# brainwave_daughter_for_kossel_mini.net
KiCad netlist of a schematic drawn in EAGLE
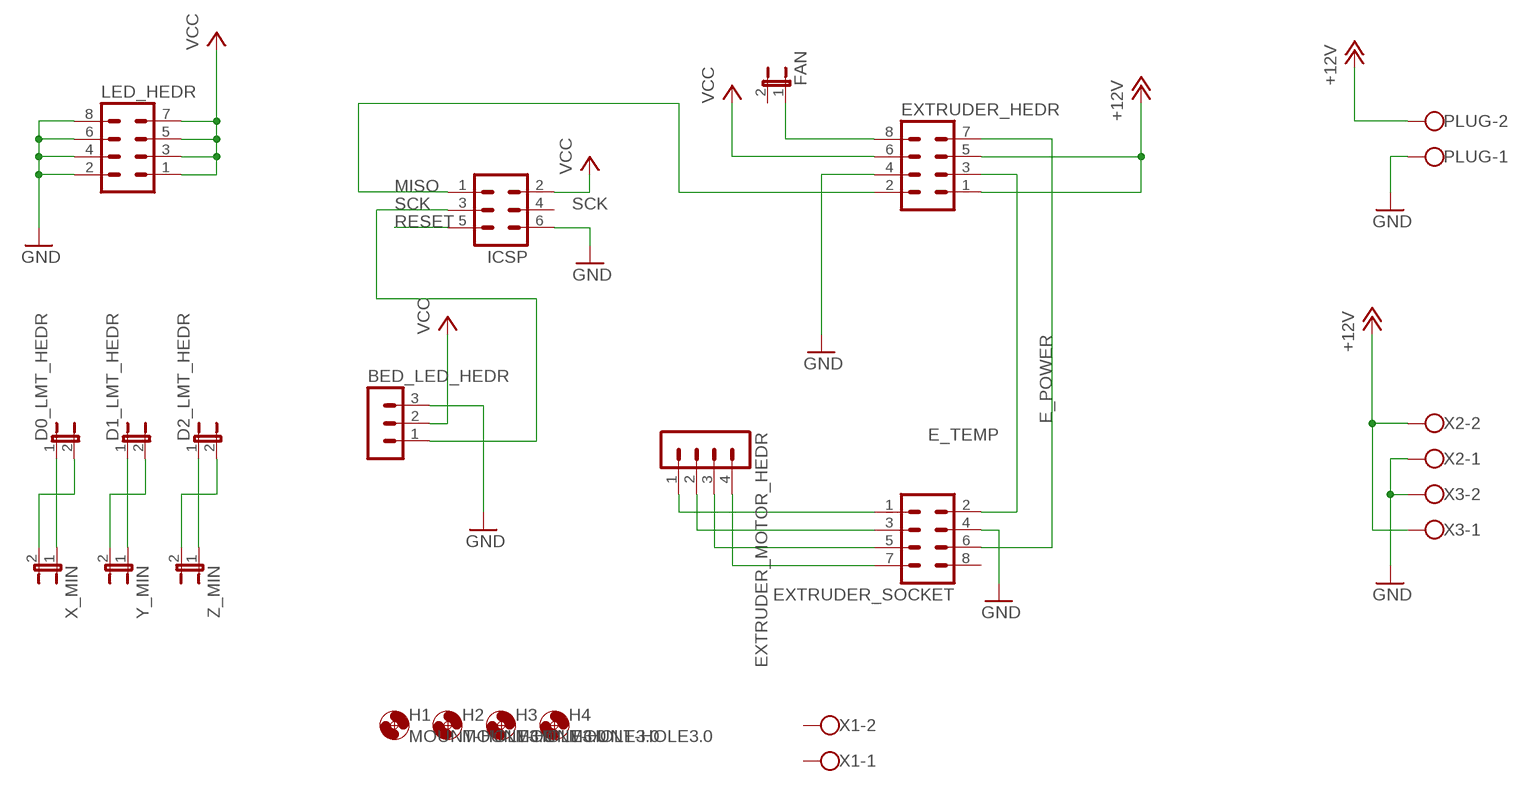
[diagram p0: schematic, sheet 1]

(export (version "E")
  (design (tool "Eeschema 10.0.6"))
  (components
    (comp (ref "BED_LED_HEDR")
      (value "MA03-1")
      (footprint "eagle-import:MA03-1")
      (libsource (lib "eagle-import") (part "MA03-1"))
    )
    (comp (ref "D0_LMT_HEDR")
      (value "JP1E")
      (footprint "eagle-import:JP1")
      (libsource (lib "eagle-import") (part "JP1E"))
    )
    (comp (ref "D1_LMT_HEDR")
      (value "JP1E")
      (footprint "eagle-import:JP1")
      (libsource (lib "eagle-import") (part "JP1E"))
    )
    (comp (ref "D2_LMT_HEDR")
      (value "JP1E")
      (footprint "eagle-import:JP1")
      (libsource (lib "eagle-import") (part "JP1E"))
    )
    (comp (ref "EXTRUDER_HEDR")
      (value "MA04-2")
      (footprint "eagle-import:MA04-2")
      (libsource (lib "eagle-import") (part "MA04-2"))
    )
    (comp (ref "EXTRUDER_MOTOR_HEDR")
      (value "MA04-1")
      (footprint "eagle-import:MA04-1")
      (libsource (lib "eagle-import") (part "MA04-1"))
    )
    (comp (ref "EXTRUDER_SOCKET")
      (value "MA04-2")
      (footprint "eagle-import:MA04-2")
      (libsource (lib "eagle-import") (part "MA04-2"))
    )
    (comp (ref "FAN")
      (value "JP1E")
      (footprint "eagle-import:JP1")
      (libsource (lib "eagle-import") (part "JP1E"))
    )
    (comp (ref "H1")
      (value "MOUNT-HOLE3.0")
      (footprint "eagle-import:3,0")
      (libsource (lib "eagle-import") (part "MOUNT-HOLE3.0"))
    )
    (comp (ref "H2")
      (value "MOUNT-HOLE3.0")
      (footprint "eagle-import:3,0")
      (libsource (lib "eagle-import") (part "MOUNT-HOLE3.0"))
    )
    (comp (ref "H3")
      (value "MOUNT-HOLE3.0")
      (footprint "eagle-import:3,0")
      (libsource (lib "eagle-import") (part "MOUNT-HOLE3.0"))
    )
    (comp (ref "H4")
      (value "MOUNT-HOLE3.0")
      (footprint "eagle-import:3,0")
      (libsource (lib "eagle-import") (part "MOUNT-HOLE3.0"))
    )
    (comp (ref "ICSP")
      (value "MA03-2")
      (footprint "eagle-import:MA03-2")
      (libsource (lib "eagle-import") (part "MA03-2"))
    )
    (comp (ref "LED_HEDR")
      (value "MA04-2")
      (footprint "eagle-import:MA04-2")
      (libsource (lib "eagle-import") (part "MA04-2"))
    )
    (comp (ref "PLUG")
      (value "W237-102")
      (footprint "eagle-import:W237-102")
      (fields (field (name "MPN") "237-102"))
      (libsource (lib "eagle-import") (part "W237-102"))
    )
    (comp (ref "X1")
      (value "W237-102")
      (footprint "eagle-import:W237-102")
      (fields
        (field (name "MPN") "237-102")
        (field (name "MPN_1") "237-102")
        (field (name "OC_FARNELL") "unknown")
        (field (name "OC_NEWARK") "70K9898")
      )
      (libsource (lib "eagle-import") (part "W237-102"))
    )
    (comp (ref "X2")
      (value "W237-102")
      (footprint "eagle-import:W237-102")
      (fields (field (name "MPN") "237-102"))
      (libsource (lib "eagle-import") (part "W237-102"))
    )
    (comp (ref "X3")
      (value "W237-102")
      (footprint "eagle-import:W237-102")
      (fields
        (field (name "MPN") "237-102")
        (field (name "MPN_1") "237-102")
        (field (name "OC_FARNELL") "unknown")
        (field (name "OC_NEWARK") "70K9898")
      )
      (libsource (lib "eagle-import") (part "W237-102"))
    )
    (comp (ref "X_MIN")
      (value "JP1E")
      (footprint "eagle-import:JP1")
      (libsource (lib "eagle-import") (part "JP1E"))
    )
    (comp (ref "Y_MIN")
      (value "JP1E")
      (footprint "eagle-import:JP1")
      (libsource (lib "eagle-import") (part "JP1E"))
    )
    (comp (ref "Z_MIN")
      (value "JP1E")
      (footprint "eagle-import:JP1")
      (libsource (lib "eagle-import") (part "JP1E"))
    )
  )
  (nets
    (net (code "1") (name "+12V") (class "Default")
      (node (ref "EXTRUDER_HEDR") (pin "1") (pinfunction "1_1") (pintype "passive"))
      (node (ref "EXTRUDER_HEDR") (pin "5") (pinfunction "5_5") (pintype "passive"))
      (node (ref "PLUG") (pin "2") (pinfunction "KL_2") (pintype "passive"))
      (node (ref "X2") (pin "2") (pinfunction "KL_2") (pintype "passive"))
      (node (ref "X3") (pin "1") (pinfunction "KL_1") (pintype "passive"))
    )
    (net (code "2") (name "/E_POWER") (class "Default")
      (node (ref "EXTRUDER_HEDR") (pin "7") (pinfunction "7_7") (pintype "passive"))
      (node (ref "EXTRUDER_SOCKET") (pin "6") (pinfunction "6_6") (pintype "passive"))
    )
    (net (code "3") (name "/E_TEMP") (class "Default")
      (node (ref "EXTRUDER_HEDR") (pin "3") (pinfunction "3_3") (pintype "passive"))
      (node (ref "EXTRUDER_SOCKET") (pin "2") (pinfunction "2_2") (pintype "passive"))
    )
    (net (code "4") (name "/MISO") (class "Default")
      (node (ref "EXTRUDER_HEDR") (pin "2") (pinfunction "2_2") (pintype "passive"))
      (node (ref "ICSP") (pin "1") (pinfunction "1_1") (pintype "passive"))
    )
    (net (code "5") (name "/RESET") (class "Default")
      (node (ref "ICSP") (pin "5") (pinfunction "5_5") (pintype "passive"))
    )
    (net (code "6") (name "/SCK") (class "Default")
      (node (ref "BED_LED_HEDR") (pin "1") (pinfunction "1_1") (pintype "passive"))
      (node (ref "ICSP") (pin "3") (pinfunction "3_3") (pintype "passive"))
    )
    (net (code "7") (name "GND") (class "Default")
      (node (ref "BED_LED_HEDR") (pin "3") (pinfunction "3_3") (pintype "passive"))
      (node (ref "EXTRUDER_HEDR") (pin "4") (pinfunction "4_4") (pintype "passive"))
      (node (ref "EXTRUDER_SOCKET") (pin "4") (pinfunction "4_4") (pintype "passive"))
      (node (ref "ICSP") (pin "6") (pinfunction "6_6") (pintype "passive"))
      (node (ref "LED_HEDR") (pin "2") (pinfunction "2_2") (pintype "passive"))
      (node (ref "LED_HEDR") (pin "4") (pinfunction "4_4") (pintype "passive"))
      (node (ref "LED_HEDR") (pin "6") (pinfunction "6_6") (pintype "passive"))
      (node (ref "LED_HEDR") (pin "8") (pinfunction "8_8") (pintype "passive"))
      (node (ref "PLUG") (pin "1") (pinfunction "KL_1") (pintype "passive"))
      (node (ref "X2") (pin "1") (pinfunction "KL_1") (pintype "passive"))
      (node (ref "X3") (pin "2") (pinfunction "KL_2") (pintype "passive"))
    )
    (net (code "8") (name "Net-(D0_LMT_HEDR-Pad1)") (class "Default")
      (node (ref "D0_LMT_HEDR") (pin "1") (pinfunction "1_1") (pintype "passive"))
      (node (ref "X_MIN") (pin "1") (pinfunction "1_1") (pintype "passive"))
    )
    (net (code "9") (name "Net-(D0_LMT_HEDR-Pad2)") (class "Default")
      (node (ref "D0_LMT_HEDR") (pin "2") (pinfunction "2_2") (pintype "passive"))
      (node (ref "X_MIN") (pin "2") (pinfunction "2_2") (pintype "passive"))
    )
    (net (code "10") (name "Net-(D1_LMT_HEDR-Pad1)") (class "Default")
      (node (ref "D1_LMT_HEDR") (pin "1") (pinfunction "1_1") (pintype "passive"))
      (node (ref "Y_MIN") (pin "1") (pinfunction "1_1") (pintype "passive"))
    )
    (net (code "11") (name "Net-(D1_LMT_HEDR-Pad2)") (class "Default")
      (node (ref "D1_LMT_HEDR") (pin "2") (pinfunction "2_2") (pintype "passive"))
      (node (ref "Y_MIN") (pin "2") (pinfunction "2_2") (pintype "passive"))
    )
    (net (code "12") (name "Net-(D2_LMT_HEDR-Pad1)") (class "Default")
      (node (ref "D2_LMT_HEDR") (pin "1") (pinfunction "1_1") (pintype "passive"))
      (node (ref "Z_MIN") (pin "1") (pinfunction "1_1") (pintype "passive"))
    )
    (net (code "13") (name "Net-(D2_LMT_HEDR-Pad2)") (class "Default")
      (node (ref "D2_LMT_HEDR") (pin "2") (pinfunction "2_2") (pintype "passive"))
      (node (ref "Z_MIN") (pin "2") (pinfunction "2_2") (pintype "passive"))
    )
    (net (code "14") (name "Net-(EXTRUDER_HEDR-Pad8)") (class "Default")
      (node (ref "EXTRUDER_HEDR") (pin "8") (pinfunction "8_8") (pintype "passive"))
      (node (ref "FAN") (pin "1") (pinfunction "1_1") (pintype "passive"))
    )
    (net (code "15") (name "Net-(EXTRUDER_MOTOR_HEDR-Pad1)") (class "Default")
      (node (ref "EXTRUDER_MOTOR_HEDR") (pin "1") (pinfunction "1_1") (pintype "passive"))
      (node (ref "EXTRUDER_SOCKET") (pin "1") (pinfunction "1_1") (pintype "passive"))
    )
    (net (code "16") (name "Net-(EXTRUDER_MOTOR_HEDR-Pad2)") (class "Default")
      (node (ref "EXTRUDER_MOTOR_HEDR") (pin "2") (pinfunction "2_2") (pintype "passive"))
      (node (ref "EXTRUDER_SOCKET") (pin "3") (pinfunction "3_3") (pintype "passive"))
    )
    (net (code "17") (name "Net-(EXTRUDER_MOTOR_HEDR-Pad3)") (class "Default")
      (node (ref "EXTRUDER_MOTOR_HEDR") (pin "3") (pinfunction "3_3") (pintype "passive"))
      (node (ref "EXTRUDER_SOCKET") (pin "5") (pinfunction "5_5") (pintype "passive"))
    )
    (net (code "18") (name "Net-(EXTRUDER_MOTOR_HEDR-Pad4)") (class "Default")
      (node (ref "EXTRUDER_MOTOR_HEDR") (pin "4") (pinfunction "4_4") (pintype "passive"))
      (node (ref "EXTRUDER_SOCKET") (pin "7") (pinfunction "7_7") (pintype "passive"))
    )
    (net (code "19") (name "VCC") (class "Default")
      (node (ref "BED_LED_HEDR") (pin "2") (pinfunction "2_2") (pintype "passive"))
      (node (ref "EXTRUDER_HEDR") (pin "6") (pinfunction "6_6") (pintype "passive"))
      (node (ref "ICSP") (pin "2") (pinfunction "2_2") (pintype "passive"))
      (node (ref "LED_HEDR") (pin "1") (pinfunction "1_1") (pintype "passive"))
      (node (ref "LED_HEDR") (pin "3") (pinfunction "3_3") (pintype "passive"))
      (node (ref "LED_HEDR") (pin "5") (pinfunction "5_5") (pintype "passive"))
      (node (ref "LED_HEDR") (pin "7") (pinfunction "7_7") (pintype "passive"))
    )
    (net (code "20") (name "unconnected-(EXTRUDER_SOCKET-Pad8)") (class "Default")
      (node (ref "EXTRUDER_SOCKET") (pin "8") (pinfunction "8_8") (pintype "passive"))
    )
    (net (code "21") (name "unconnected-(FAN-Pad2)") (class "Default")
      (node (ref "FAN") (pin "2") (pinfunction "2_2") (pintype "passive"))
    )
    (net (code "22") (name "unconnected-(ICSP-Pad4)") (class "Default")
      (node (ref "ICSP") (pin "4") (pinfunction "4_4") (pintype "passive"))
    )
    (net (code "23") (name "unconnected-(X1A-KL-Pad1)") (class "Default")
      (node (ref "X1") (pin "1") (pinfunction "KL_1") (pintype "passive"))
    )
    (net (code "24") (name "unconnected-(X1B-KL-Pad2)") (class "Default")
      (node (ref "X1") (pin "2") (pinfunction "KL_2") (pintype "passive"))
    )
  )
)
